# ProPrj_vTally32-Multi_2024-12-10.net
KiCad netlist of a schematic drawn in EasyEDA Pro
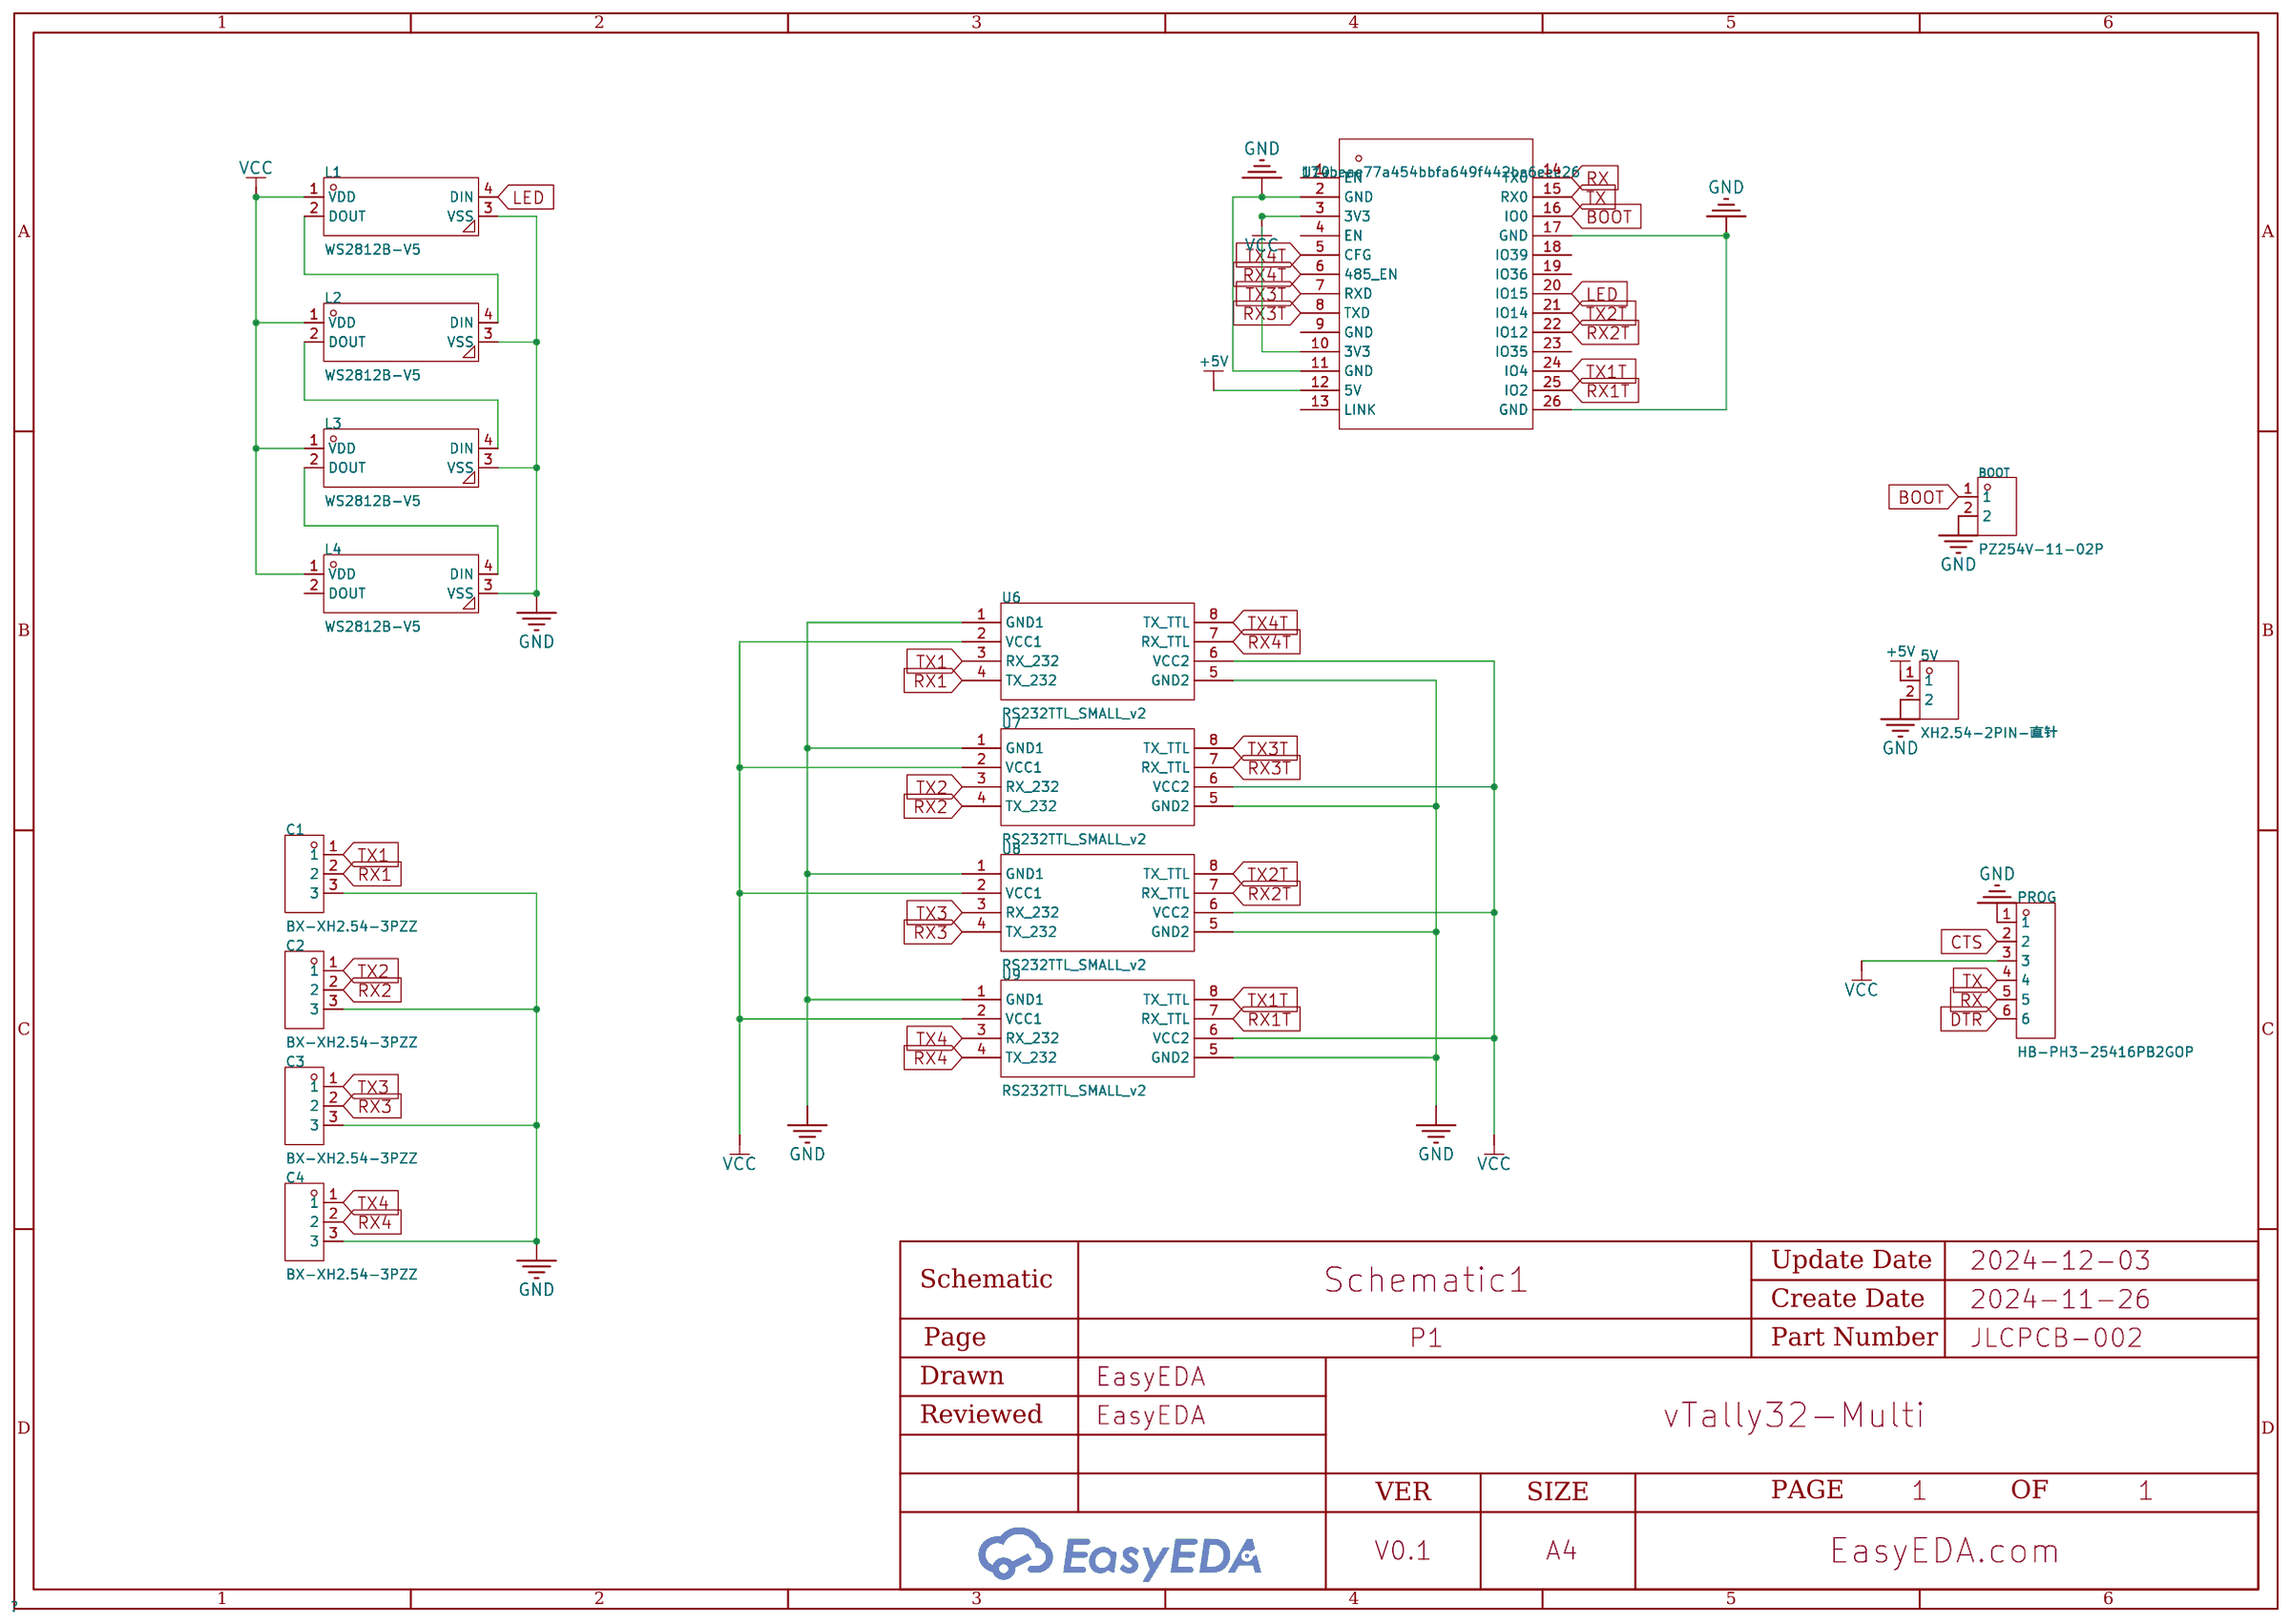
[diagram p0: schematic sheet]

(export (version "E")
  (design (tool "Eeschema 10.0.6"))
  (components
    (comp (ref "5V")
      (value "XH2.54-2PIN-直针")
      (footprint "easyedapro:CONN-TH_XH2.54-2P")
      (libsource (lib "easyedapro") (part "XH2.54-2PIN-直针"))
    )
    (comp (ref "BOOT")
      (value "PZ254V-11-02P")
      (footprint "easyedapro:HDR-TH_2P-P2.54-V-M")
      (fields (field (name "Manufacturer") "XFCN(兴飞)"))
      (libsource (lib "easyedapro") (part "PZ254V-11-02P"))
    )
    (comp (ref "C1")
      (value "BX-XH2.54-3PZZ")
      (footprint "easyedapro:CONN-TH_3P-P2.50_BX-XH2.54-3PZZ")
      (fields (field (name "Manufacturer") "Bossie(博锡)"))
      (libsource (lib "easyedapro") (part "BX-XH2.54-3PZZ"))
    )
    (comp (ref "C2")
      (value "BX-XH2.54-3PZZ")
      (footprint "easyedapro:CONN-TH_3P-P2.50_BX-XH2.54-3PZZ")
      (fields (field (name "Manufacturer") "Bossie(博锡)"))
      (libsource (lib "easyedapro") (part "BX-XH2.54-3PZZ"))
    )
    (comp (ref "C3")
      (value "BX-XH2.54-3PZZ")
      (footprint "easyedapro:CONN-TH_3P-P2.50_BX-XH2.54-3PZZ")
      (fields (field (name "Manufacturer") "Bossie(博锡)"))
      (libsource (lib "easyedapro") (part "BX-XH2.54-3PZZ"))
    )
    (comp (ref "C4")
      (value "BX-XH2.54-3PZZ")
      (footprint "easyedapro:CONN-TH_3P-P2.50_BX-XH2.54-3PZZ")
      (fields (field (name "Manufacturer") "Bossie(博锡)"))
      (libsource (lib "easyedapro") (part "BX-XH2.54-3PZZ"))
    )
    (comp (ref "L1")
      (value "WS2812B-V5")
      (footprint "easyedapro:LED-SMD_4P-L5.0-W5.0-LS5.4-TL-1")
      (fields (field (name "Manufacturer") "worldsemi"))
      (libsource (lib "easyedapro") (part "WS2812B-V5_C2846931"))
    )
    (comp (ref "L2")
      (value "WS2812B-V5")
      (footprint "easyedapro:LED-SMD_4P-L5.0-W5.0-LS5.4-TL-1")
      (fields (field (name "Manufacturer") "worldsemi"))
      (libsource (lib "easyedapro") (part "WS2812B-V5_C2846931"))
    )
    (comp (ref "L3")
      (value "WS2812B-V5")
      (footprint "easyedapro:LED-SMD_4P-L5.0-W5.0-LS5.4-TL-1")
      (fields (field (name "Manufacturer") "worldsemi"))
      (libsource (lib "easyedapro") (part "WS2812B-V5_C2846931"))
    )
    (comp (ref "L4")
      (value "WS2812B-V5")
      (footprint "easyedapro:LED-SMD_4P-L5.0-W5.0-LS5.4-TL-1")
      (fields (field (name "Manufacturer") "worldsemi"))
      (libsource (lib "easyedapro") (part "WS2812B-V5_C2846931"))
    )
    (comp (ref "PROG")
      (value "HB-PH3-25416PB2GOP")
      (footprint "easyedapro:HDR-TH_6P-P2.54-V-M")
      (fields (field (name "Manufacturer") "HANBO(汉博)"))
      (libsource (lib "easyedapro") (part "HB-PH3-25416PB2GOP"))
    )
    (comp (ref "U6")
      (value "RS232TTL_SMALL_v2")
      (footprint "easyedapro:RS232TTL_SMALL")
      (libsource (lib "easyedapro") (part "RS232TTL_SMALL_v2"))
    )
    (comp (ref "U7")
      (value "RS232TTL_SMALL_v2")
      (footprint "easyedapro:RS232TTL_SMALL")
      (libsource (lib "easyedapro") (part "RS232TTL_SMALL_v2"))
    )
    (comp (ref "U8")
      (value "RS232TTL_SMALL_v2")
      (footprint "easyedapro:RS232TTL_SMALL")
      (libsource (lib "easyedapro") (part "RS232TTL_SMALL_v2"))
    )
    (comp (ref "U9")
      (value "RS232TTL_SMALL_v2")
      (footprint "easyedapro:RS232TTL_SMALL")
      (libsource (lib "easyedapro") (part "RS232TTL_SMALL_v2"))
    )
    (comp (ref "U10")
      (value "174beae77a454bbfa649f442be6eee26")
      (footprint "easyedapro:WT32-ETH01")
      (description "Wireless-tag WT32-ETH01")
      (libsource (lib "easyedapro") (part "WT32-ETH01"))
    )
  )
  (nets
    (net (code "1") (name "+5V") (class "Default")
      (node (ref "5V") (pin "1") (pinfunction "1_1") (pintype "unspecified"))
      (node (ref "U10") (pin "12") (pinfunction "5V_12") (pintype "input"))
    )
    (net (code "2") (name "BOOT") (class "Default")
      (node (ref "BOOT") (pin "1") (pinfunction "1_1") (pintype "input"))
      (node (ref "U10") (pin "16") (pinfunction "IO0_16") (pintype "input"))
    )
    (net (code "3") (name "CTS") (class "Default")
      (node (ref "PROG") (pin "2") (pinfunction "2_2") (pintype "unspecified"))
    )
    (net (code "4") (name "DTR") (class "Default")
      (node (ref "PROG") (pin "6") (pinfunction "6_6") (pintype "unspecified"))
    )
    (net (code "5") (name "GND") (class "Default")
      (node (ref "5V") (pin "2") (pinfunction "2_2") (pintype "unspecified"))
      (node (ref "BOOT") (pin "2") (pinfunction "2_2") (pintype "input"))
      (node (ref "C1") (pin "3") (pinfunction "3_3") (pintype "unspecified"))
      (node (ref "C2") (pin "3") (pinfunction "3_3") (pintype "unspecified"))
      (node (ref "C3") (pin "3") (pinfunction "3_3") (pintype "unspecified"))
      (node (ref "C4") (pin "3") (pinfunction "3_3") (pintype "unspecified"))
      (node (ref "L1") (pin "3") (pinfunction "VSS_3") (pintype "unspecified"))
      (node (ref "L2") (pin "3") (pinfunction "VSS_3") (pintype "unspecified"))
      (node (ref "L3") (pin "3") (pinfunction "VSS_3") (pintype "unspecified"))
      (node (ref "L4") (pin "3") (pinfunction "VSS_3") (pintype "unspecified"))
      (node (ref "PROG") (pin "1") (pinfunction "1_1") (pintype "unspecified"))
      (node (ref "U10") (pin "11") (pinfunction "GND_11") (pintype "input"))
      (node (ref "U10") (pin "17") (pinfunction "GND_17") (pintype "input"))
      (node (ref "U10") (pin "2") (pinfunction "GND_2") (pintype "input"))
      (node (ref "U10") (pin "26") (pinfunction "GND_26") (pintype "input"))
      (node (ref "U6") (pin "1") (pinfunction "GND1_1") (pintype "unspecified"))
      (node (ref "U6") (pin "5") (pinfunction "GND2_5") (pintype "unspecified"))
      (node (ref "U7") (pin "1") (pinfunction "GND1_1") (pintype "unspecified"))
      (node (ref "U7") (pin "5") (pinfunction "GND2_5") (pintype "unspecified"))
      (node (ref "U8") (pin "1") (pinfunction "GND1_1") (pintype "unspecified"))
      (node (ref "U8") (pin "5") (pinfunction "GND2_5") (pintype "unspecified"))
      (node (ref "U9") (pin "1") (pinfunction "GND1_1") (pintype "unspecified"))
      (node (ref "U9") (pin "5") (pinfunction "GND2_5") (pintype "unspecified"))
    )
    (net (code "6") (name "LED") (class "Default")
      (node (ref "L1") (pin "4") (pinfunction "DIN_4") (pintype "unspecified"))
      (node (ref "U10") (pin "20") (pinfunction "IO15_20") (pintype "input"))
    )
    (net (code "7") (name "Net-(L1-DOUT)") (class "Default")
      (node (ref "L1") (pin "2") (pinfunction "DOUT_2") (pintype "unspecified"))
      (node (ref "L2") (pin "4") (pinfunction "DIN_4") (pintype "unspecified"))
    )
    (net (code "8") (name "Net-(L2-DOUT)") (class "Default")
      (node (ref "L2") (pin "2") (pinfunction "DOUT_2") (pintype "unspecified"))
      (node (ref "L3") (pin "4") (pinfunction "DIN_4") (pintype "unspecified"))
    )
    (net (code "9") (name "Net-(L3-DOUT)") (class "Default")
      (node (ref "L3") (pin "2") (pinfunction "DOUT_2") (pintype "unspecified"))
      (node (ref "L4") (pin "4") (pinfunction "DIN_4") (pintype "unspecified"))
    )
    (net (code "10") (name "RX") (class "Default")
      (node (ref "PROG") (pin "5") (pinfunction "5_5") (pintype "unspecified"))
      (node (ref "U10") (pin "14") (pinfunction "TX0_14") (pintype "input"))
    )
    (net (code "11") (name "RX1") (class "Default")
      (node (ref "C1") (pin "2") (pinfunction "2_2") (pintype "unspecified"))
      (node (ref "U6") (pin "4") (pinfunction "TX_232_4") (pintype "unspecified"))
    )
    (net (code "12") (name "RX1T") (class "Default")
      (node (ref "U10") (pin "25") (pinfunction "IO2_25") (pintype "input"))
      (node (ref "U9") (pin "7") (pinfunction "RX_TTL_7") (pintype "unspecified"))
    )
    (net (code "13") (name "RX2") (class "Default")
      (node (ref "C2") (pin "2") (pinfunction "2_2") (pintype "unspecified"))
      (node (ref "U7") (pin "4") (pinfunction "TX_232_4") (pintype "unspecified"))
    )
    (net (code "14") (name "RX2T") (class "Default")
      (node (ref "U10") (pin "22") (pinfunction "IO12_22") (pintype "input"))
      (node (ref "U8") (pin "7") (pinfunction "RX_TTL_7") (pintype "unspecified"))
    )
    (net (code "15") (name "RX3") (class "Default")
      (node (ref "C3") (pin "2") (pinfunction "2_2") (pintype "unspecified"))
      (node (ref "U8") (pin "4") (pinfunction "TX_232_4") (pintype "unspecified"))
    )
    (net (code "16") (name "RX3T") (class "Default")
      (node (ref "U10") (pin "8") (pinfunction "TXD_8") (pintype "input"))
      (node (ref "U7") (pin "7") (pinfunction "RX_TTL_7") (pintype "unspecified"))
    )
    (net (code "17") (name "RX4") (class "Default")
      (node (ref "C4") (pin "2") (pinfunction "2_2") (pintype "unspecified"))
      (node (ref "U9") (pin "4") (pinfunction "TX_232_4") (pintype "unspecified"))
    )
    (net (code "18") (name "RX4T") (class "Default")
      (node (ref "U10") (pin "6") (pinfunction "485_EN_6") (pintype "input"))
      (node (ref "U6") (pin "7") (pinfunction "RX_TTL_7") (pintype "unspecified"))
    )
    (net (code "19") (name "TX") (class "Default")
      (node (ref "PROG") (pin "4") (pinfunction "4_4") (pintype "unspecified"))
      (node (ref "U10") (pin "15") (pinfunction "RX0_15") (pintype "input"))
    )
    (net (code "20") (name "TX1") (class "Default")
      (node (ref "C1") (pin "1") (pinfunction "1_1") (pintype "unspecified"))
      (node (ref "U6") (pin "3") (pinfunction "RX_232_3") (pintype "unspecified"))
    )
    (net (code "21") (name "TX1T") (class "Default")
      (node (ref "U10") (pin "24") (pinfunction "IO4_24") (pintype "input"))
      (node (ref "U9") (pin "8") (pinfunction "TX_TTL_8") (pintype "unspecified"))
    )
    (net (code "22") (name "TX2") (class "Default")
      (node (ref "C2") (pin "1") (pinfunction "1_1") (pintype "unspecified"))
      (node (ref "U7") (pin "3") (pinfunction "RX_232_3") (pintype "unspecified"))
    )
    (net (code "23") (name "TX2T") (class "Default")
      (node (ref "U10") (pin "21") (pinfunction "IO14_21") (pintype "input"))
      (node (ref "U8") (pin "8") (pinfunction "TX_TTL_8") (pintype "unspecified"))
    )
    (net (code "24") (name "TX3") (class "Default")
      (node (ref "C3") (pin "1") (pinfunction "1_1") (pintype "unspecified"))
      (node (ref "U8") (pin "3") (pinfunction "RX_232_3") (pintype "unspecified"))
    )
    (net (code "25") (name "TX3T") (class "Default")
      (node (ref "U10") (pin "7") (pinfunction "RXD_7") (pintype "input"))
      (node (ref "U7") (pin "8") (pinfunction "TX_TTL_8") (pintype "unspecified"))
    )
    (net (code "26") (name "TX4") (class "Default")
      (node (ref "C4") (pin "1") (pinfunction "1_1") (pintype "unspecified"))
      (node (ref "U9") (pin "3") (pinfunction "RX_232_3") (pintype "unspecified"))
    )
    (net (code "27") (name "TX4T") (class "Default")
      (node (ref "U10") (pin "5") (pinfunction "CFG_5") (pintype "input"))
      (node (ref "U6") (pin "8") (pinfunction "TX_TTL_8") (pintype "unspecified"))
    )
    (net (code "28") (name "VCC") (class "Default")
      (node (ref "L1") (pin "1") (pinfunction "VDD_1") (pintype "unspecified"))
      (node (ref "L2") (pin "1") (pinfunction "VDD_1") (pintype "unspecified"))
      (node (ref "L3") (pin "1") (pinfunction "VDD_1") (pintype "unspecified"))
      (node (ref "L4") (pin "1") (pinfunction "VDD_1") (pintype "unspecified"))
      (node (ref "PROG") (pin "3") (pinfunction "3_3") (pintype "unspecified"))
      (node (ref "U10") (pin "10") (pinfunction "3V3_10") (pintype "input"))
      (node (ref "U10") (pin "3") (pinfunction "3V3_3") (pintype "input"))
      (node (ref "U6") (pin "2") (pinfunction "VCC1_2") (pintype "unspecified"))
      (node (ref "U6") (pin "6") (pinfunction "VCC2_6") (pintype "unspecified"))
      (node (ref "U7") (pin "2") (pinfunction "VCC1_2") (pintype "unspecified"))
      (node (ref "U7") (pin "6") (pinfunction "VCC2_6") (pintype "unspecified"))
      (node (ref "U8") (pin "2") (pinfunction "VCC1_2") (pintype "unspecified"))
      (node (ref "U8") (pin "6") (pinfunction "VCC2_6") (pintype "unspecified"))
      (node (ref "U9") (pin "2") (pinfunction "VCC1_2") (pintype "unspecified"))
      (node (ref "U9") (pin "6") (pinfunction "VCC2_6") (pintype "unspecified"))
    )
    (net (code "29") (name "unconnected-(L4-DOUT-Pad2)") (class "Default")
      (node (ref "L4") (pin "2") (pinfunction "DOUT_2") (pintype "unspecified"))
    )
    (net (code "30") (name "unconnected-(U10-EN-Pad1)") (class "Default")
      (node (ref "U10") (pin "1") (pinfunction "EN_1") (pintype "input"))
    )
    (net (code "31") (name "unconnected-(U10-EN-Pad4)") (class "Default")
      (node (ref "U10") (pin "4") (pinfunction "EN_4") (pintype "input"))
    )
    (net (code "32") (name "unconnected-(U10-GND-Pad9)") (class "Default")
      (node (ref "U10") (pin "9") (pinfunction "GND_9") (pintype "input"))
    )
    (net (code "33") (name "unconnected-(U10-IO35-Pad23)") (class "Default")
      (node (ref "U10") (pin "23") (pinfunction "IO35_23") (pintype "input"))
    )
    (net (code "34") (name "unconnected-(U10-IO36-Pad19)") (class "Default")
      (node (ref "U10") (pin "19") (pinfunction "IO36_19") (pintype "input"))
    )
    (net (code "35") (name "unconnected-(U10-IO39-Pad18)") (class "Default")
      (node (ref "U10") (pin "18") (pinfunction "IO39_18") (pintype "input"))
    )
    (net (code "36") (name "unconnected-(U10-LINK-Pad13)") (class "Default")
      (node (ref "U10") (pin "13") (pinfunction "LINK_13") (pintype "input"))
    )
  )
)
